# timer_arduino_two.net
KiCad netlist of a schematic drawn in EAGLE
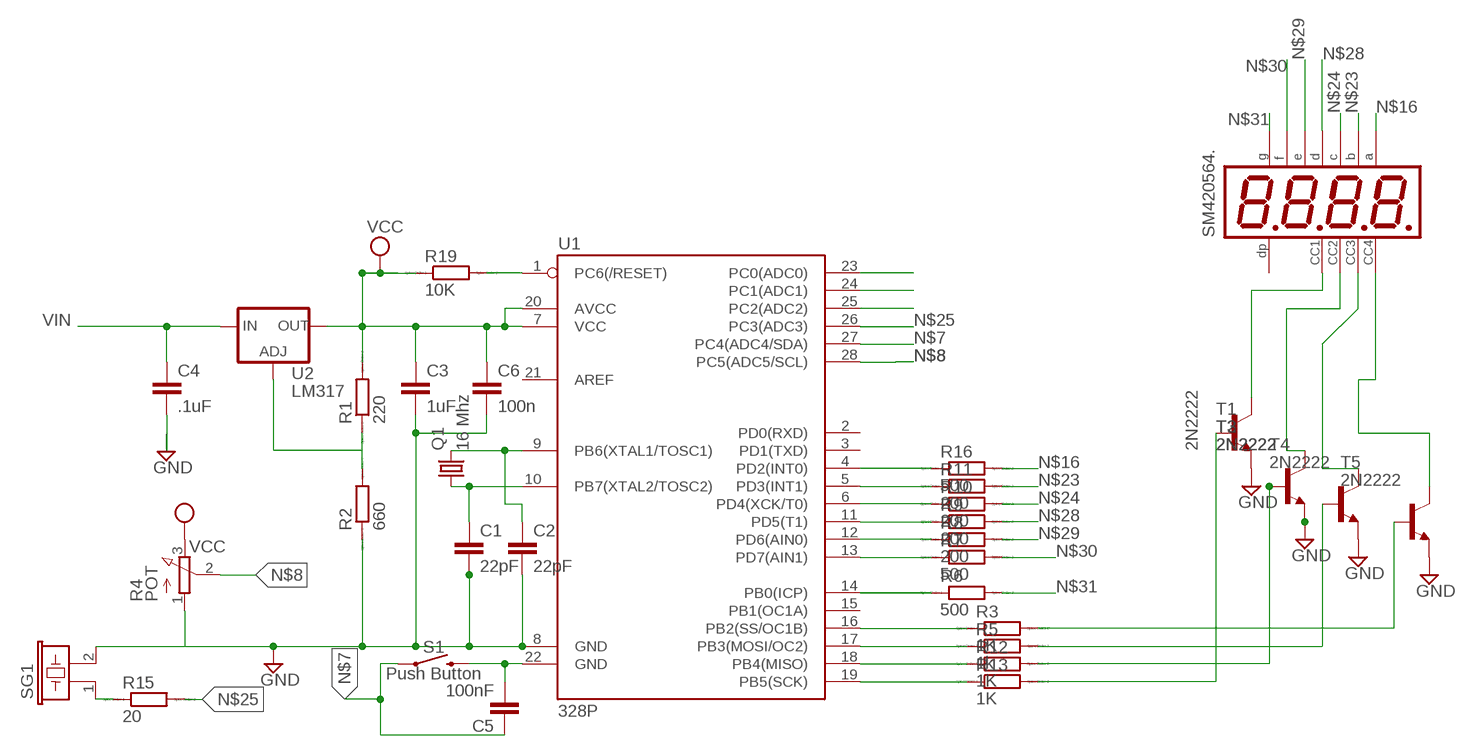
[diagram p0: schematic, sheet 1]

(export (version "E")
  (design (tool "Eeschema 10.0.6"))
  (components
    (comp (ref "C1")
      (value "22pF")
      (footprint "eagle-import:C2.5-3")
      (libsource (lib "eagle-import") (part "C2,5-3"))
    )
    (comp (ref "C2")
      (value "22pF")
      (footprint "eagle-import:C2.5-3")
      (libsource (lib "eagle-import") (part "C2,5-3"))
    )
    (comp (ref "C3")
      (value "1uF")
      (footprint "eagle-import:C2.5-3")
      (libsource (lib "eagle-import") (part "C2,5-3"))
    )
    (comp (ref "C4")
      (value ".1uF")
      (footprint "eagle-import:C2.5-3")
      (libsource (lib "eagle-import") (part "C2,5-3"))
    )
    (comp (ref "C5")
      (value "100nF")
      (footprint "eagle-import:C2.5-3")
      (libsource (lib "eagle-import") (part "C2,5-3"))
    )
    (comp (ref "C6")
      (value "100n")
      (footprint "eagle-import:C2.5-3")
      (libsource (lib "eagle-import") (part "C2,5-3"))
    )
    (comp (ref "Q1")
      (value "16 Mhz")
      (footprint "eagle-import:HC18U-V")
      (libsource (lib "eagle-import") (part "CRYSTALHC18U-V"))
    )
    (comp (ref "R1")
      (value "220")
      (footprint "eagle-import:R2010")
      (libsource (lib "eagle-import") (part "RR2010"))
    )
    (comp (ref "R2")
      (value "660")
      (footprint "eagle-import:R2010")
      (libsource (lib "eagle-import") (part "RR2010"))
    )
    (comp (ref "R3")
      (value "1K")
      (footprint "eagle-import:R0805")
      (libsource (lib "eagle-import") (part "R"))
    )
    (comp (ref "R4")
      (value "POT")
      (footprint "eagle-import:3RP_1610N")
      (libsource (lib "eagle-import") (part "3RP/1610N"))
    )
    (comp (ref "R5")
      (value "1k")
      (footprint "eagle-import:R0805")
      (libsource (lib "eagle-import") (part "R"))
    )
    (comp (ref "R6")
      (value "500")
      (footprint "eagle-import:R0805")
      (libsource (lib "eagle-import") (part "R"))
    )
    (comp (ref "R7")
      (value "500")
      (footprint "eagle-import:R0805")
      (libsource (lib "eagle-import") (part "R"))
    )
    (comp (ref "R8")
      (value "200")
      (footprint "eagle-import:R0805")
      (libsource (lib "eagle-import") (part "R"))
    )
    (comp (ref "R9")
      (value "200")
      (footprint "eagle-import:R0805")
      (libsource (lib "eagle-import") (part "R"))
    )
    (comp (ref "R10")
      (value "200")
      (footprint "eagle-import:R0805")
      (libsource (lib "eagle-import") (part "R"))
    )
    (comp (ref "R11")
      (value "200")
      (footprint "eagle-import:R0805")
      (libsource (lib "eagle-import") (part "R"))
    )
    (comp (ref "R12")
      (value "1K")
      (footprint "eagle-import:R0805")
      (libsource (lib "eagle-import") (part "R"))
    )
    (comp (ref "R13")
      (value "1K")
      (footprint "eagle-import:R0805")
      (libsource (lib "eagle-import") (part "R"))
    )
    (comp (ref "R15")
      (value "20")
      (footprint "eagle-import:R0402")
      (libsource (lib "eagle-import") (part "RR0402"))
    )
    (comp (ref "R16")
      (value "500")
      (footprint "eagle-import:R0805")
      (libsource (lib "eagle-import") (part "R"))
    )
    (comp (ref "R19")
      (value "10K")
      (footprint "eagle-import:R0402")
      (libsource (lib "eagle-import") (part "RR0402"))
    )
    (comp (ref "S1")
      (value "Push Button")
      (footprint "eagle-import:TACTILE_SWITCH_PTH_6.0MM")
      (libsource (lib "eagle-import") (part "MOMENTARY-SWITCH-SPST-PTH-6.0MM"))
    )
    (comp (ref "SG1")
      (value "B/C11L")
      (footprint "eagle-import:B_C11L")
      (libsource (lib "eagle-import") (part "B/C11L"))
    )
    (comp (ref "SM420564.")
      (value "NFD-5641AS")
      (footprint "eagle-import:NFD-5641")
      (libsource (lib "eagle-import") (part "NFD-5641AS"))
    )
    (comp (ref "T1")
      (value "2N2222")
      (footprint "eagle-import:TO18")
      (libsource (lib "eagle-import") (part "2N2222"))
    )
    (comp (ref "T2")
      (value "2N2222")
      (footprint "eagle-import:TO18")
      (libsource (lib "eagle-import") (part "2N2222"))
    )
    (comp (ref "T3")
      (value "2N2222")
      (footprint "eagle-import:TO18")
      (libsource (lib "eagle-import") (part "2N2222"))
    )
    (comp (ref "T4")
      (value "2N2222")
      (footprint "eagle-import:TO18")
      (libsource (lib "eagle-import") (part "2N2222"))
    )
    (comp (ref "T5")
      (value "2N2222")
      (footprint "eagle-import:TO18")
      (libsource (lib "eagle-import") (part "2N2222"))
    )
    (comp (ref "U1")
      (value "328P")
      (footprint "eagle-import:DIP28")
      (libsource (lib "eagle-import") (part "ATMEGA328P_PDIP"))
    )
    (comp (ref "U2")
      (value "LM317")
      (footprint "eagle-import:V-REG_DPACK")
      (libsource (lib "eagle-import") (part "V_REG_317DPACK"))
    )
  )
  (nets
    (net (code "1") (name "/N$16") (class "Default")
      (node (ref "R16") (pin "2") (pinfunction "2_2") (pintype "passive"))
      (node (ref "SM420564.") (pin "P$11") (pinfunction "P$11_P$11") (pintype "bidirectional"))
    )
    (net (code "2") (name "/N$23") (class "Default")
      (node (ref "R11") (pin "2") (pinfunction "2_2") (pintype "passive"))
      (node (ref "SM420564.") (pin "P$7") (pinfunction "P$7_P$7") (pintype "bidirectional"))
    )
    (net (code "3") (name "/N$24") (class "Default")
      (node (ref "R10") (pin "2") (pinfunction "2_2") (pintype "passive"))
      (node (ref "SM420564.") (pin "P$4") (pinfunction "P$4_P$4") (pintype "bidirectional"))
    )
    (net (code "4") (name "/N$28") (class "Default")
      (node (ref "R9") (pin "2") (pinfunction "2_2") (pintype "passive"))
      (node (ref "SM420564.") (pin "P$2") (pinfunction "P$2_P$2") (pintype "bidirectional"))
    )
    (net (code "5") (name "/N$29") (class "Default")
      (node (ref "R8") (pin "2") (pinfunction "2_2") (pintype "passive"))
      (node (ref "SM420564.") (pin "P$1") (pinfunction "P$1_P$1") (pintype "bidirectional"))
    )
    (net (code "6") (name "/N$30") (class "Default")
      (node (ref "R7") (pin "2") (pinfunction "2_2") (pintype "passive"))
      (node (ref "SM420564.") (pin "P$10") (pinfunction "P$10_P$10") (pintype "bidirectional"))
    )
    (net (code "7") (name "/N$31") (class "Default")
      (node (ref "R6") (pin "2") (pinfunction "2_2") (pintype "passive"))
      (node (ref "SM420564.") (pin "P$5") (pinfunction "P$5_P$5") (pintype "bidirectional"))
    )
    (net (code "8") (name "/VIN") (class "Default")
      (node (ref "C4") (pin "1") (pinfunction "1_1") (pintype "passive"))
      (node (ref "U2") (pin "3") (pinfunction "IN_3") (pintype "input"))
    )
    (net (code "9") (name "GND") (class "Default")
      (node (ref "C1") (pin "2") (pinfunction "2_2") (pintype "passive"))
      (node (ref "C2") (pin "2") (pinfunction "2_2") (pintype "passive"))
      (node (ref "C3") (pin "2") (pinfunction "2_2") (pintype "passive"))
      (node (ref "C6") (pin "2") (pinfunction "2_2") (pintype "passive"))
      (node (ref "R2") (pin "1") (pinfunction "1_1") (pintype "passive"))
      (node (ref "R4") (pin "1") (pinfunction "A_1") (pintype "passive"))
      (node (ref "SG1") (pin "2") (pinfunction "2_2") (pintype "passive"))
      (node (ref "T1") (pin "1") (pinfunction "E_1") (pintype "passive"))
      (node (ref "T2") (pin "1") (pinfunction "E_1") (pintype "passive"))
      (node (ref "T3") (pin "1") (pinfunction "E_1") (pintype "passive"))
      (node (ref "T4") (pin "1") (pinfunction "E_1") (pintype "passive"))
      (node (ref "T5") (pin "1") (pinfunction "E_1") (pintype "passive"))
      (node (ref "U1") (pin "8") (pinfunction "GND_8") (pintype "bidirectional"))
    )
    (net (code "10") (name "N$7") (class "Default")
      (node (ref "U1") (pin "27") (pinfunction "PC4(ADC4/SDA)_27") (pintype "bidirectional"))
    )
    (net (code "11") (name "N$8") (class "Default")
      (node (ref "R4") (pin "2") (pinfunction "S_2") (pintype "passive"))
      (node (ref "U1") (pin "28") (pinfunction "PC5(ADC5/SCL)_28") (pintype "bidirectional"))
    )
    (net (code "12") (name "N$25") (class "Default")
      (node (ref "R15") (pin "2") (pinfunction "2_2") (pintype "passive"))
    )
    (net (code "13") (name "Net-(C5-Pad1)") (class "Default")
      (node (ref "C5") (pin "1") (pinfunction "1_1") (pintype "passive"))
      (node (ref "S1") (pin "1") (pinfunction "1_1") (pintype "passive"))
    )
    (net (code "14") (name "Net-(R1-Pad1)") (class "Default")
      (node (ref "R1") (pin "1") (pinfunction "1_1") (pintype "passive"))
      (node (ref "R2") (pin "2") (pinfunction "2_2") (pintype "passive"))
    )
    (net (code "15") (name "Net-(R15-Pad1)") (class "Default")
      (node (ref "R15") (pin "1") (pinfunction "1_1") (pintype "passive"))
      (node (ref "SG1") (pin "1") (pinfunction "1_1") (pintype "passive"))
    )
    (net (code "16") (name "Net-(S1-2)") (class "Default")
      (node (ref "C5") (pin "2") (pinfunction "2_2") (pintype "passive"))
      (node (ref "S1") (pin "3") (pinfunction "2_3") (pintype "passive"))
      (node (ref "U1") (pin "22") (pinfunction "GND_22") (pintype "bidirectional"))
    )
    (net (code "17") (name "Net-(T1-B)") (class "Default")
      (node (ref "R13") (pin "2") (pinfunction "2_2") (pintype "passive"))
      (node (ref "T1") (pin "2") (pinfunction "B_2") (pintype "passive"))
    )
    (net (code "18") (name "Net-(T1-C)") (class "Default")
      (node (ref "SM420564.") (pin "P$12") (pinfunction "P$12_P$12") (pintype "bidirectional"))
      (node (ref "T1") (pin "3") (pinfunction "C_3") (pintype "passive"))
    )
    (net (code "19") (name "Net-(T2-B)") (class "Default")
      (node (ref "R12") (pin "2") (pinfunction "2_2") (pintype "passive"))
      (node (ref "T2") (pin "2") (pinfunction "B_2") (pintype "passive"))
      (node (ref "T3") (pin "2") (pinfunction "B_2") (pintype "passive"))
    )
    (net (code "20") (name "Net-(T2-C)") (class "Default")
      (node (ref "SM420564.") (pin "P$9") (pinfunction "P$9_P$9") (pintype "bidirectional"))
      (node (ref "T2") (pin "3") (pinfunction "C_3") (pintype "passive"))
      (node (ref "T3") (pin "3") (pinfunction "C_3") (pintype "passive"))
    )
    (net (code "21") (name "Net-(T4-B)") (class "Default")
      (node (ref "R5") (pin "2") (pinfunction "2_2") (pintype "passive"))
      (node (ref "T4") (pin "2") (pinfunction "B_2") (pintype "passive"))
    )
    (net (code "22") (name "Net-(T4-C)") (class "Default")
      (node (ref "SM420564.") (pin "P$8") (pinfunction "P$8_P$8") (pintype "bidirectional"))
      (node (ref "T4") (pin "3") (pinfunction "C_3") (pintype "passive"))
    )
    (net (code "23") (name "Net-(T5-B)") (class "Default")
      (node (ref "R3") (pin "2") (pinfunction "2_2") (pintype "passive"))
      (node (ref "T5") (pin "2") (pinfunction "B_2") (pintype "passive"))
    )
    (net (code "24") (name "Net-(T5-C)") (class "Default")
      (node (ref "SM420564.") (pin "P$6") (pinfunction "P$6_P$6") (pintype "bidirectional"))
      (node (ref "T5") (pin "3") (pinfunction "C_3") (pintype "passive"))
    )
    (net (code "25") (name "Net-(U1-PB0(ICP))") (class "Default")
      (node (ref "R6") (pin "1") (pinfunction "1_1") (pintype "passive"))
      (node (ref "U1") (pin "14") (pinfunction "PB0(ICP)_14") (pintype "bidirectional"))
    )
    (net (code "26") (name "Net-(U1-PB2(SS{slash}OC1B))") (class "Default")
      (node (ref "R3") (pin "1") (pinfunction "1_1") (pintype "passive"))
      (node (ref "U1") (pin "16") (pinfunction "PB2(SS/OC1B)_16") (pintype "bidirectional"))
    )
    (net (code "27") (name "Net-(U1-PB3(MOSI{slash}OC2))") (class "Default")
      (node (ref "R5") (pin "1") (pinfunction "1_1") (pintype "passive"))
      (node (ref "U1") (pin "17") (pinfunction "PB3(MOSI/OC2)_17") (pintype "bidirectional"))
    )
    (net (code "28") (name "Net-(U1-PB4(MISO))") (class "Default")
      (node (ref "R12") (pin "1") (pinfunction "1_1") (pintype "passive"))
      (node (ref "U1") (pin "18") (pinfunction "PB4(MISO)_18") (pintype "bidirectional"))
    )
    (net (code "29") (name "Net-(U1-PB5(SCK))") (class "Default")
      (node (ref "R13") (pin "1") (pinfunction "1_1") (pintype "passive"))
      (node (ref "U1") (pin "19") (pinfunction "PB5(SCK)_19") (pintype "bidirectional"))
    )
    (net (code "30") (name "Net-(U1-PB6(XTAL1{slash}TOSC1))") (class "Default")
      (node (ref "C2") (pin "1") (pinfunction "1_1") (pintype "passive"))
      (node (ref "Q1") (pin "2") (pinfunction "2_2") (pintype "passive"))
      (node (ref "U1") (pin "9") (pinfunction "PB6(XTAL1/TOSC1)_9") (pintype "bidirectional"))
    )
    (net (code "31") (name "Net-(U1-PB7(XTAL2{slash}TOSC2))") (class "Default")
      (node (ref "C1") (pin "1") (pinfunction "1_1") (pintype "passive"))
      (node (ref "Q1") (pin "1") (pinfunction "1_1") (pintype "passive"))
      (node (ref "U1") (pin "10") (pinfunction "PB7(XTAL2/TOSC2)_10") (pintype "bidirectional"))
    )
    (net (code "32") (name "Net-(U1-PC6({slash}RESET))") (class "Default")
      (node (ref "R19") (pin "2") (pinfunction "2_2") (pintype "passive"))
      (node (ref "U1") (pin "1") (pinfunction "PC6(/RESET)_1") (pintype "bidirectional"))
    )
    (net (code "33") (name "Net-(U1-PD2(INT0))") (class "Default")
      (node (ref "R16") (pin "1") (pinfunction "1_1") (pintype "passive"))
      (node (ref "U1") (pin "4") (pinfunction "PD2(INT0)_4") (pintype "bidirectional"))
    )
    (net (code "34") (name "Net-(U1-PD3(INT1))") (class "Default")
      (node (ref "R11") (pin "1") (pinfunction "1_1") (pintype "passive"))
      (node (ref "U1") (pin "5") (pinfunction "PD3(INT1)_5") (pintype "bidirectional"))
    )
    (net (code "35") (name "Net-(U1-PD4(XCK{slash}T0))") (class "Default")
      (node (ref "R10") (pin "1") (pinfunction "1_1") (pintype "passive"))
      (node (ref "U1") (pin "6") (pinfunction "PD4(XCK/T0)_6") (pintype "bidirectional"))
    )
    (net (code "36") (name "Net-(U1-PD5(T1))") (class "Default")
      (node (ref "R9") (pin "1") (pinfunction "1_1") (pintype "passive"))
      (node (ref "U1") (pin "11") (pinfunction "PD5(T1)_11") (pintype "bidirectional"))
    )
    (net (code "37") (name "Net-(U1-PD6(AIN0))") (class "Default")
      (node (ref "R8") (pin "1") (pinfunction "1_1") (pintype "passive"))
      (node (ref "U1") (pin "12") (pinfunction "PD6(AIN0)_12") (pintype "bidirectional"))
    )
    (net (code "38") (name "Net-(U1-PD7(AIN1))") (class "Default")
      (node (ref "R7") (pin "1") (pinfunction "1_1") (pintype "passive"))
      (node (ref "U1") (pin "13") (pinfunction "PD7(AIN1)_13") (pintype "bidirectional"))
    )
    (net (code "39") (name "VCC") (class "Default")
      (node (ref "C3") (pin "1") (pinfunction "1_1") (pintype "passive"))
      (node (ref "C6") (pin "1") (pinfunction "1_1") (pintype "passive"))
      (node (ref "R1") (pin "2") (pinfunction "2_2") (pintype "passive"))
      (node (ref "R19") (pin "1") (pinfunction "1_1") (pintype "passive"))
      (node (ref "R4") (pin "3") (pinfunction "E_3") (pintype "passive"))
      (node (ref "U1") (pin "20") (pinfunction "AVCC_20") (pintype "bidirectional"))
      (node (ref "U1") (pin "7") (pinfunction "VCC_7") (pintype "bidirectional"))
      (node (ref "U2") (pin "4") (pinfunction "OUT_4") (pintype "output"))
    )
    (net (code "40") (name "unconnected-(C4-Pad2)") (class "Default")
      (node (ref "C4") (pin "2") (pinfunction "2_2") (pintype "passive"))
    )
    (net (code "41") (name "unconnected-(SM420564.-PadP$3)") (class "Default")
      (node (ref "SM420564.") (pin "P$3") (pinfunction "P$3_P$3") (pintype "bidirectional"))
    )
    (net (code "42") (name "unconnected-(U1-AREF-Pad21)") (class "Default")
      (node (ref "U1") (pin "21") (pinfunction "AREF_21") (pintype "bidirectional"))
    )
    (net (code "43") (name "unconnected-(U1-PB1(OC1A)-Pad15)") (class "Default")
      (node (ref "U1") (pin "15") (pinfunction "PB1(OC1A)_15") (pintype "bidirectional"))
    )
    (net (code "44") (name "unconnected-(U1-PC0(ADC0)-Pad23)") (class "Default")
      (node (ref "U1") (pin "23") (pinfunction "PC0(ADC0)_23") (pintype "bidirectional"))
    )
    (net (code "45") (name "unconnected-(U1-PC1(ADC1)-Pad24)") (class "Default")
      (node (ref "U1") (pin "24") (pinfunction "PC1(ADC1)_24") (pintype "bidirectional"))
    )
    (net (code "46") (name "unconnected-(U1-PC2(ADC2)-Pad25)") (class "Default")
      (node (ref "U1") (pin "25") (pinfunction "PC2(ADC2)_25") (pintype "bidirectional"))
    )
    (net (code "47") (name "unconnected-(U1-PC3(ADC3)-Pad26)") (class "Default")
      (node (ref "U1") (pin "26") (pinfunction "PC3(ADC3)_26") (pintype "bidirectional"))
    )
    (net (code "48") (name "unconnected-(U1-PD0(RXD)-Pad2)") (class "Default")
      (node (ref "U1") (pin "2") (pinfunction "PD0(RXD)_2") (pintype "bidirectional"))
    )
    (net (code "49") (name "unconnected-(U1-PD1(TXD)-Pad3)") (class "Default")
      (node (ref "U1") (pin "3") (pinfunction "PD1(TXD)_3") (pintype "bidirectional"))
    )
    (net (code "50") (name "unconnected-(U2-ADJ-Pad1)") (class "Default")
      (node (ref "U2") (pin "1") (pinfunction "ADJ_1") (pintype "input"))
    )
  )
)
